# traffic_lights.net
KiCad netlist of a schematic drawn in EAGLE
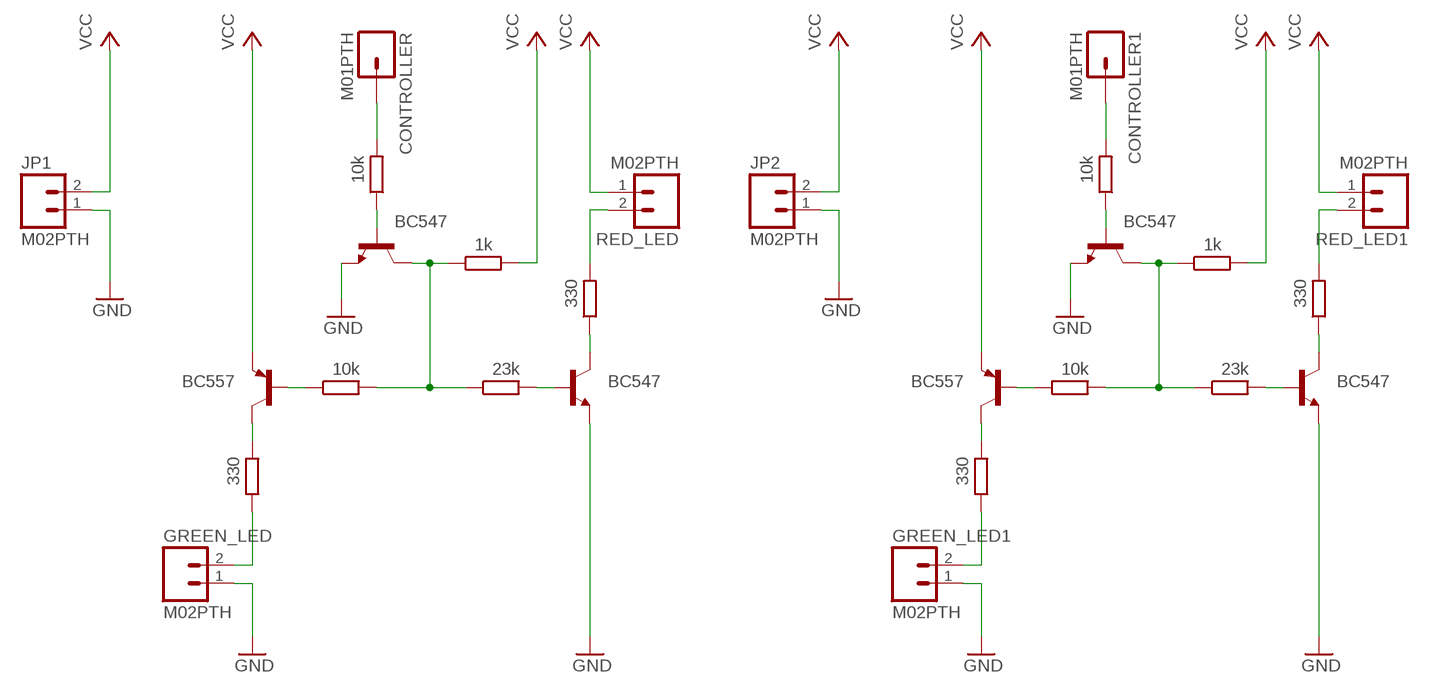
[diagram p0: schematic, sheet 1]

(export (version "E")
  (design (tool "Eeschema 10.0.6"))
  (components
    (comp (ref "CONTROLLER")
      (value "M01PTH")
      (footprint "eagle-import:1X01")
      (libsource (lib "eagle-import") (part "M01PTH"))
    )
    (comp (ref "CONTROLLER1")
      (value "M01PTH")
      (footprint "eagle-import:1X01")
      (libsource (lib "eagle-import") (part "M01PTH"))
    )
    (comp (ref "GREEN_LED")
      (value "M02PTH")
      (footprint "eagle-import:1X02")
      (libsource (lib "eagle-import") (part "M02PTH"))
    )
    (comp (ref "GREEN_LED1")
      (value "M02PTH")
      (footprint "eagle-import:1X02")
      (libsource (lib "eagle-import") (part "M02PTH"))
    )
    (comp (ref "JP1")
      (value "M02PTH")
      (footprint "eagle-import:1X02")
      (libsource (lib "eagle-import") (part "M02PTH"))
    )
    (comp (ref "JP2")
      (value "M02PTH")
      (footprint "eagle-import:1X02")
      (libsource (lib "eagle-import") (part "M02PTH"))
    )
    (comp (ref "Q1")
      (value "BC557")
      (footprint "eagle-import:TO92")
      (libsource (lib "eagle-import") (part "BC557"))
    )
    (comp (ref "Q2")
      (value "BC557")
      (footprint "eagle-import:TO92")
      (libsource (lib "eagle-import") (part "BC557"))
    )
    (comp (ref "R1")
      (value "10k")
      (footprint "eagle-import:0207_10")
      (libsource (lib "eagle-import") (part "R-EU_0207/10"))
    )
    (comp (ref "R2")
      (value "10k")
      (footprint "eagle-import:0207_10")
      (libsource (lib "eagle-import") (part "R-EU_0207/10"))
    )
    (comp (ref "R3")
      (value "23k")
      (footprint "eagle-import:0207_10")
      (libsource (lib "eagle-import") (part "R-EU_0207/10"))
    )
    (comp (ref "R4")
      (value "23k")
      (footprint "eagle-import:0207_10")
      (libsource (lib "eagle-import") (part "R-EU_0207/10"))
    )
    (comp (ref "R5")
      (value "10k")
      (footprint "eagle-import:0207_10")
      (libsource (lib "eagle-import") (part "R-EU_0207/10"))
    )
    (comp (ref "R6")
      (value "1k")
      (footprint "eagle-import:0207_10")
      (libsource (lib "eagle-import") (part "R-EU_0207/10"))
    )
    (comp (ref "R7")
      (value "330")
      (footprint "eagle-import:0207_10")
      (libsource (lib "eagle-import") (part "R-EU_0207/10"))
    )
    (comp (ref "R8")
      (value "10k")
      (footprint "eagle-import:0207_10")
      (libsource (lib "eagle-import") (part "R-EU_0207/10"))
    )
    (comp (ref "R9")
      (value "1k")
      (footprint "eagle-import:0207_10")
      (libsource (lib "eagle-import") (part "R-EU_0207/10"))
    )
    (comp (ref "R10")
      (value "330")
      (footprint "eagle-import:0207_10")
      (libsource (lib "eagle-import") (part "R-EU_0207/10"))
    )
    (comp (ref "R11")
      (value "330")
      (footprint "eagle-import:0207_10")
      (libsource (lib "eagle-import") (part "R-EU_0207/10"))
    )
    (comp (ref "R12")
      (value "330")
      (footprint "eagle-import:0207_10")
      (libsource (lib "eagle-import") (part "R-EU_0207/10"))
    )
    (comp (ref "RED_LED")
      (value "M02PTH")
      (footprint "eagle-import:1X02")
      (libsource (lib "eagle-import") (part "M02PTH"))
    )
    (comp (ref "RED_LED1")
      (value "M02PTH")
      (footprint "eagle-import:1X02")
      (libsource (lib "eagle-import") (part "M02PTH"))
    )
    (comp (ref "T1")
      (value "BC547")
      (footprint "eagle-import:TO92")
      (libsource (lib "eagle-import") (part "BC547"))
    )
    (comp (ref "T2")
      (value "BC547")
      (footprint "eagle-import:TO92")
      (libsource (lib "eagle-import") (part "BC547"))
    )
    (comp (ref "T3")
      (value "BC547")
      (footprint "eagle-import:TO92")
      (libsource (lib "eagle-import") (part "BC547"))
    )
    (comp (ref "T4")
      (value "BC547")
      (footprint "eagle-import:TO92")
      (libsource (lib "eagle-import") (part "BC547"))
    )
  )
  (nets
    (net (code "1") (name "GND") (class "Default")
      (node (ref "GREEN_LED") (pin "1") (pinfunction "1_1") (pintype "passive"))
      (node (ref "GREEN_LED1") (pin "1") (pinfunction "1_1") (pintype "passive"))
      (node (ref "JP1") (pin "1") (pinfunction "1_1") (pintype "passive"))
      (node (ref "JP2") (pin "1") (pinfunction "1_1") (pintype "passive"))
      (node (ref "T1") (pin "1") (pinfunction "E_1") (pintype "passive"))
      (node (ref "T2") (pin "1") (pinfunction "E_1") (pintype "passive"))
      (node (ref "T3") (pin "1") (pinfunction "E_1") (pintype "passive"))
      (node (ref "T4") (pin "1") (pinfunction "E_1") (pintype "passive"))
    )
    (net (code "2") (name "Net-(CONTROLLER-Pad1)") (class "Default")
      (node (ref "CONTROLLER") (pin "1") (pinfunction "1_1") (pintype "passive"))
      (node (ref "R8") (pin "2") (pinfunction "2_2") (pintype "passive"))
    )
    (net (code "3") (name "Net-(CONTROLLER1-Pad1)") (class "Default")
      (node (ref "CONTROLLER1") (pin "1") (pinfunction "1_1") (pintype "passive"))
      (node (ref "R5") (pin "2") (pinfunction "2_2") (pintype "passive"))
    )
    (net (code "4") (name "Net-(GREEN_LED-Pad2)") (class "Default")
      (node (ref "GREEN_LED") (pin "2") (pinfunction "2_2") (pintype "passive"))
      (node (ref "R11") (pin "1") (pinfunction "1_1") (pintype "passive"))
    )
    (net (code "5") (name "Net-(GREEN_LED1-Pad2)") (class "Default")
      (node (ref "GREEN_LED1") (pin "2") (pinfunction "2_2") (pintype "passive"))
      (node (ref "R12") (pin "1") (pinfunction "1_1") (pintype "passive"))
    )
    (net (code "6") (name "Net-(Q1-B)") (class "Default")
      (node (ref "Q1") (pin "2") (pinfunction "B_2") (pintype "passive"))
      (node (ref "R2") (pin "1") (pinfunction "1_1") (pintype "passive"))
    )
    (net (code "7") (name "Net-(Q1-C)") (class "Default")
      (node (ref "Q1") (pin "3") (pinfunction "C_3") (pintype "passive"))
      (node (ref "R11") (pin "2") (pinfunction "2_2") (pintype "passive"))
    )
    (net (code "8") (name "Net-(Q2-B)") (class "Default")
      (node (ref "Q2") (pin "2") (pinfunction "B_2") (pintype "passive"))
      (node (ref "R1") (pin "1") (pinfunction "1_1") (pintype "passive"))
    )
    (net (code "9") (name "Net-(Q2-C)") (class "Default")
      (node (ref "Q2") (pin "3") (pinfunction "C_3") (pintype "passive"))
      (node (ref "R12") (pin "2") (pinfunction "2_2") (pintype "passive"))
    )
    (net (code "10") (name "Net-(R7-Pad2)") (class "Default")
      (node (ref "R7") (pin "2") (pinfunction "2_2") (pintype "passive"))
      (node (ref "RED_LED1") (pin "2") (pinfunction "2_2") (pintype "passive"))
    )
    (net (code "11") (name "Net-(R10-Pad2)") (class "Default")
      (node (ref "R10") (pin "2") (pinfunction "2_2") (pintype "passive"))
      (node (ref "RED_LED") (pin "2") (pinfunction "2_2") (pintype "passive"))
    )
    (net (code "12") (name "Net-(T1-B)") (class "Default")
      (node (ref "R3") (pin "2") (pinfunction "2_2") (pintype "passive"))
      (node (ref "T1") (pin "2") (pinfunction "B_2") (pintype "passive"))
    )
    (net (code "13") (name "Net-(T1-C)") (class "Default")
      (node (ref "R10") (pin "1") (pinfunction "1_1") (pintype "passive"))
      (node (ref "T1") (pin "3") (pinfunction "C_3") (pintype "passive"))
    )
    (net (code "14") (name "Net-(T2-B)") (class "Default")
      (node (ref "R8") (pin "1") (pinfunction "1_1") (pintype "passive"))
      (node (ref "T2") (pin "2") (pinfunction "B_2") (pintype "passive"))
    )
    (net (code "15") (name "Net-(T2-C)") (class "Default")
      (node (ref "R2") (pin "2") (pinfunction "2_2") (pintype "passive"))
      (node (ref "R3") (pin "1") (pinfunction "1_1") (pintype "passive"))
      (node (ref "R9") (pin "1") (pinfunction "1_1") (pintype "passive"))
      (node (ref "T2") (pin "3") (pinfunction "C_3") (pintype "passive"))
    )
    (net (code "16") (name "Net-(T3-B)") (class "Default")
      (node (ref "R4") (pin "2") (pinfunction "2_2") (pintype "passive"))
      (node (ref "T3") (pin "2") (pinfunction "B_2") (pintype "passive"))
    )
    (net (code "17") (name "Net-(T3-C)") (class "Default")
      (node (ref "R7") (pin "1") (pinfunction "1_1") (pintype "passive"))
      (node (ref "T3") (pin "3") (pinfunction "C_3") (pintype "passive"))
    )
    (net (code "18") (name "Net-(T4-B)") (class "Default")
      (node (ref "R5") (pin "1") (pinfunction "1_1") (pintype "passive"))
      (node (ref "T4") (pin "2") (pinfunction "B_2") (pintype "passive"))
    )
    (net (code "19") (name "Net-(T4-C)") (class "Default")
      (node (ref "R1") (pin "2") (pinfunction "2_2") (pintype "passive"))
      (node (ref "R4") (pin "1") (pinfunction "1_1") (pintype "passive"))
      (node (ref "R6") (pin "1") (pinfunction "1_1") (pintype "passive"))
      (node (ref "T4") (pin "3") (pinfunction "C_3") (pintype "passive"))
    )
    (net (code "20") (name "VCC") (class "Default")
      (node (ref "JP1") (pin "2") (pinfunction "2_2") (pintype "passive"))
      (node (ref "JP2") (pin "2") (pinfunction "2_2") (pintype "passive"))
      (node (ref "Q1") (pin "1") (pinfunction "E_1") (pintype "passive"))
      (node (ref "Q2") (pin "1") (pinfunction "E_1") (pintype "passive"))
      (node (ref "R6") (pin "2") (pinfunction "2_2") (pintype "passive"))
      (node (ref "R9") (pin "2") (pinfunction "2_2") (pintype "passive"))
      (node (ref "RED_LED") (pin "1") (pinfunction "1_1") (pintype "passive"))
      (node (ref "RED_LED1") (pin "1") (pinfunction "1_1") (pintype "passive"))
    )
  )
)
